# EtherWiz_3K4KNic.net
KiCad netlist of a schematic drawn in Altium Designer
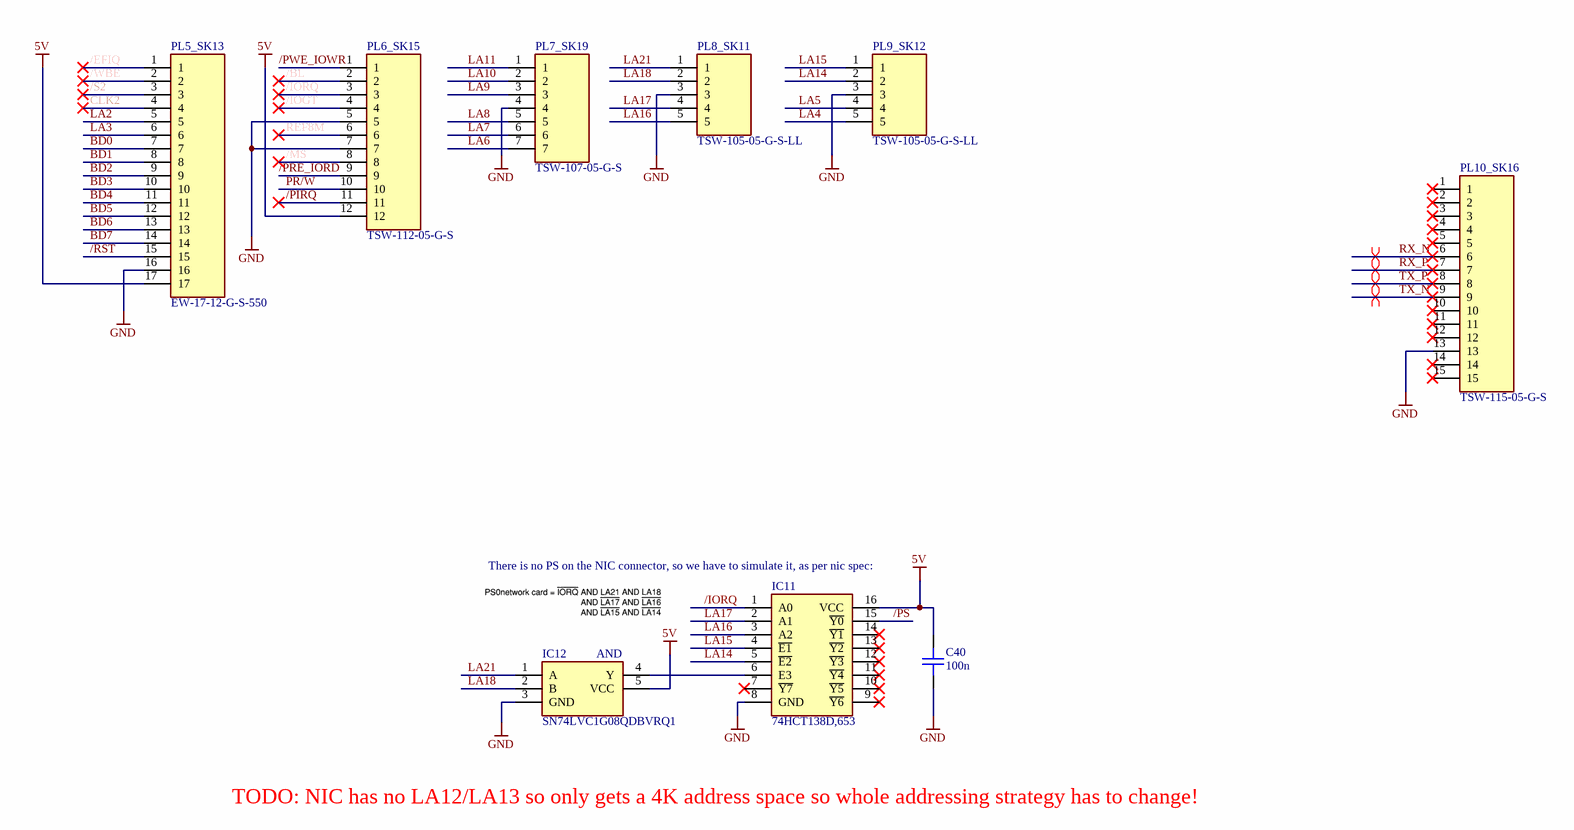
[diagram p0: EtherWiz_3K4KNic.SchDoc]

(export (version "E")
  (design (tool "Eeschema 10.0.6"))
  (components
    (comp (ref "C40")
      (value "100n")
      (footprint "CAPC1608L")
      (description "CAP 100nF, 0603, 50V, X7R, 10%")
      (fields
        (field (name "DISTRIBUTOR1 PART NO") "CL10B104KB8NNNC")
        (field (name "DISTRIBUTOR2 PART NO") "311-1344-2-ND")
      )
      (libsource (lib "MCP1002_RevC") (part "CAP_100n_0603_50V_0"))
    )
    (comp (ref "IC11")
      (value "74HCT138D,653")
      (footprint "SamacSys:SOIC127P600X175-16N")
      (description "Integrated Circuit")
      (fields (field (name "MOUSER PART NUMBER") "771-74HCT138D-T"))
      (libsource (lib "*") (part "74HCT138D,653"))
    )
    (comp (ref "IC12")
      (value "SN74LVC1G08QDBVRQ1")
      (footprint "SamacSys:SOT95P280X145-5N")
      (description "Integrated Circuit")
      (fields (field (name "MOUSER PART NUMBER") "595-SN74LVC1G08QDBQ1"))
      (libsource (lib "*") (part "SN74LVC1G08QDBVRQ1"))
    )
    (comp (ref "PL5_SK13")
      (value "EW-17-12-G-S-550")
      (footprint "SamacSys:TSW-117-XX-YY-S")
      (description "Connector")
      (fields (field (name "MANUFACTURER_PART_NUMBER") "TSW-117-05-G-S"))
      (libsource (lib "*") (part "TSW-117-05-G-S"))
    )
    (comp (ref "PL6_SK15")
      (value "TSW-112-05-G-S")
      (footprint "SamacSys:TSW-112-XX-YY-S")
      (description "Connector")
      (libsource (lib "*") (part "TSW-112-05-G-S"))
    )
    (comp (ref "PL7_SK19")
      (value "TSW-107-05-G-S")
      (footprint "SamacSys:TSW-107-XX-YY-S")
      (description "Connector")
      (libsource (lib "*") (part "TSW-107-05-G-S"))
    )
    (comp (ref "PL8_SK11")
      (value "TSW-105-05-G-S-LL")
      (footprint "SamacSys:HDRV5W64P0X254_1X5_1270X254X521P")
      (description "Connector")
      (libsource (lib "*") (part "TSW-105-05-G-S-LL"))
    )
    (comp (ref "PL9_SK12")
      (value "TSW-105-05-G-S-LL")
      (footprint "SamacSys:HDRV5W64P0X254_1X5_1270X254X521P")
      (description "Connector")
      (libsource (lib "*") (part "TSW-105-05-G-S-LL"))
    )
    (comp (ref "PL10_SK16")
      (value "TSW-115-05-G-S")
      (footprint "SamacSys:TSW-115-XX-YY-S")
      (description "Connector")
      (libsource (lib "*") (part "TSW-115-05-G-S"))
    )
  )
  (nets
    (net (code "1") (name "/BD0") (class "Default")
      (node (ref "PL5_SK13") (pin "7") (pinfunction "7_7") (pintype "passive"))
    )
    (net (code "2") (name "/BD1") (class "Default")
      (node (ref "PL5_SK13") (pin "8") (pinfunction "8_8") (pintype "passive"))
    )
    (net (code "3") (name "/BD2") (class "Default")
      (node (ref "PL5_SK13") (pin "9") (pinfunction "9_9") (pintype "passive"))
    )
    (net (code "4") (name "/BD3") (class "Default")
      (node (ref "PL5_SK13") (pin "10") (pinfunction "10_10") (pintype "passive"))
    )
    (net (code "5") (name "/BD4") (class "Default")
      (node (ref "PL5_SK13") (pin "11") (pinfunction "11_11") (pintype "passive"))
    )
    (net (code "6") (name "/BD5") (class "Default")
      (node (ref "PL5_SK13") (pin "12") (pinfunction "12_12") (pintype "passive"))
    )
    (net (code "7") (name "/BD6") (class "Default")
      (node (ref "PL5_SK13") (pin "13") (pinfunction "13_13") (pintype "passive"))
    )
    (net (code "8") (name "/BD7") (class "Default")
      (node (ref "PL5_SK13") (pin "14") (pinfunction "14_14") (pintype "passive"))
    )
    (net (code "9") (name "/CLK2") (class "Default")
      (node (ref "PL5_SK13") (pin "4") (pinfunction "4_4") (pintype "passive+no_connect"))
    )
    (net (code "10") (name "/LA2") (class "Default")
      (node (ref "PL5_SK13") (pin "5") (pinfunction "5_5") (pintype "passive"))
    )
    (net (code "11") (name "/LA3") (class "Default")
      (node (ref "PL5_SK13") (pin "6") (pinfunction "6_6") (pintype "passive"))
    )
    (net (code "12") (name "/LA4") (class "Default")
      (node (ref "PL9_SK12") (pin "5") (pinfunction "5_5") (pintype "passive"))
    )
    (net (code "13") (name "/LA5") (class "Default")
      (node (ref "PL9_SK12") (pin "4") (pinfunction "4_4") (pintype "passive"))
    )
    (net (code "14") (name "/LA6") (class "Default")
      (node (ref "PL7_SK19") (pin "7") (pinfunction "7_7") (pintype "passive"))
    )
    (net (code "15") (name "/LA7") (class "Default")
      (node (ref "PL7_SK19") (pin "6") (pinfunction "6_6") (pintype "passive"))
    )
    (net (code "16") (name "/LA8") (class "Default")
      (node (ref "PL7_SK19") (pin "5") (pinfunction "5_5") (pintype "passive"))
    )
    (net (code "17") (name "/LA9") (class "Default")
      (node (ref "PL7_SK19") (pin "3") (pinfunction "3_3") (pintype "passive"))
    )
    (net (code "18") (name "/LA10") (class "Default")
      (node (ref "PL7_SK19") (pin "2") (pinfunction "2_2") (pintype "passive"))
    )
    (net (code "19") (name "/LA11") (class "Default")
      (node (ref "PL7_SK19") (pin "1") (pinfunction "1_1") (pintype "passive"))
    )
    (net (code "20") (name "/LA14") (class "Default")
      (node (ref "IC11") (pin "5") (pinfunction "~{E2}_5") (pintype "passive"))
      (node (ref "PL9_SK12") (pin "2") (pinfunction "2_2") (pintype "passive"))
    )
    (net (code "21") (name "/LA15") (class "Default")
      (node (ref "IC11") (pin "4") (pinfunction "~{E1}_4") (pintype "passive"))
      (node (ref "PL9_SK12") (pin "1") (pinfunction "1_1") (pintype "passive"))
    )
    (net (code "22") (name "/LA16") (class "Default")
      (node (ref "IC11") (pin "3") (pinfunction "A2_3") (pintype "passive"))
      (node (ref "PL8_SK11") (pin "5") (pinfunction "5_5") (pintype "passive"))
    )
    (net (code "23") (name "/LA17") (class "Default")
      (node (ref "IC11") (pin "2") (pinfunction "A1_2") (pintype "passive"))
      (node (ref "PL8_SK11") (pin "4") (pinfunction "4_4") (pintype "passive"))
    )
    (net (code "24") (name "/LA18") (class "Default")
      (node (ref "IC12") (pin "2") (pinfunction "B_2") (pintype "passive"))
      (node (ref "PL8_SK11") (pin "2") (pinfunction "2_2") (pintype "passive"))
    )
    (net (code "25") (name "/LA21") (class "Default")
      (node (ref "IC12") (pin "1") (pinfunction "A_1") (pintype "passive"))
      (node (ref "PL8_SK11") (pin "1") (pinfunction "1_1") (pintype "passive"))
    )
    (net (code "26") (name "/PR{slash}W") (class "Default")
      (node (ref "PL6_SK15") (pin "10") (pinfunction "10_10") (pintype "passive"))
    )
    (net (code "27") (name "/REF8M") (class "Default")
      (node (ref "PL6_SK15") (pin "6") (pinfunction "6_6") (pintype "passive+no_connect"))
    )
    (net (code "28") (name "/RX_N") (class "Default")
      (node (ref "PL10_SK16") (pin "6") (pinfunction "6_6") (pintype "passive+no_connect"))
    )
    (net (code "29") (name "/RX_P") (class "Default")
      (node (ref "PL10_SK16") (pin "7") (pinfunction "7_7") (pintype "passive+no_connect"))
    )
    (net (code "30") (name "/TX_N") (class "Default")
      (node (ref "PL10_SK16") (pin "9") (pinfunction "9_9") (pintype "passive+no_connect"))
    )
    (net (code "31") (name "/TX_P") (class "Default")
      (node (ref "PL10_SK16") (pin "8") (pinfunction "8_8") (pintype "passive+no_connect"))
    )
    (net (code "32") (name "/{slash}BL") (class "Default")
      (node (ref "PL6_SK15") (pin "2") (pinfunction "2_2") (pintype "passive+no_connect"))
    )
    (net (code "33") (name "/{slash}EFIQ") (class "Default")
      (node (ref "PL5_SK13") (pin "1") (pinfunction "1_1") (pintype "passive+no_connect"))
    )
    (net (code "34") (name "/{slash}IOGT") (class "Default")
      (node (ref "PL6_SK15") (pin "4") (pinfunction "4_4") (pintype "passive+no_connect"))
    )
    (net (code "35") (name "/{slash}IORQ") (class "Default")
      (node (ref "IC11") (pin "1") (pinfunction "A0_1") (pintype "passive"))
      (node (ref "PL6_SK15") (pin "3") (pinfunction "3_3") (pintype "passive"))
    )
    (net (code "36") (name "/{slash}MS") (class "Default")
      (node (ref "PL6_SK15") (pin "8") (pinfunction "8_8") (pintype "passive+no_connect"))
    )
    (net (code "37") (name "/{slash}PIRQ") (class "Default")
      (node (ref "PL6_SK15") (pin "11") (pinfunction "11_11") (pintype "passive+no_connect"))
    )
    (net (code "38") (name "/{slash}PRE_IORD") (class "Default")
      (node (ref "PL6_SK15") (pin "9") (pinfunction "9_9") (pintype "passive"))
    )
    (net (code "39") (name "/{slash}PS") (class "Default")
      (node (ref "IC11") (pin "15") (pinfunction "~{Y0}_15") (pintype "passive"))
    )
    (net (code "40") (name "/{slash}PWE_IOWR") (class "Default")
      (node (ref "PL6_SK15") (pin "1") (pinfunction "1_1") (pintype "passive"))
    )
    (net (code "41") (name "/{slash}RST") (class "Default")
      (node (ref "PL5_SK13") (pin "15") (pinfunction "15_15") (pintype "passive"))
    )
    (net (code "42") (name "/{slash}S2") (class "Default")
      (node (ref "PL5_SK13") (pin "3") (pinfunction "3_3") (pintype "passive+no_connect"))
    )
    (net (code "43") (name "/{slash}WBE") (class "Default")
      (node (ref "PL5_SK13") (pin "2") (pinfunction "2_2") (pintype "passive+no_connect"))
    )
    (net (code "44") (name "5V") (class "Default")
      (node (ref "C40") (pin "2") (pintype "passive"))
      (node (ref "IC11") (pin "16") (pinfunction "VCC_16") (pintype "passive"))
      (node (ref "IC12") (pin "5") (pinfunction "VCC_5") (pintype "power_in"))
      (node (ref "PL5_SK13") (pin "17") (pinfunction "17_17") (pintype "passive"))
      (node (ref "PL6_SK15") (pin "12") (pinfunction "12_12") (pintype "passive"))
    )
    (net (code "45") (name "GND") (class "Default")
      (node (ref "C40") (pin "1") (pintype "passive"))
      (node (ref "IC11") (pin "8") (pinfunction "GND_8") (pintype "passive"))
      (node (ref "IC12") (pin "3") (pinfunction "GND_3") (pintype "power_in"))
      (node (ref "PL10_SK16") (pin "13") (pinfunction "13_13") (pintype "passive"))
      (node (ref "PL5_SK13") (pin "16") (pinfunction "16_16") (pintype "passive"))
      (node (ref "PL6_SK15") (pin "5") (pinfunction "5_5") (pintype "passive"))
      (node (ref "PL6_SK15") (pin "7") (pinfunction "7_7") (pintype "passive"))
      (node (ref "PL7_SK19") (pin "4") (pinfunction "4_4") (pintype "passive"))
      (node (ref "PL8_SK11") (pin "3") (pinfunction "3_3") (pintype "passive"))
      (node (ref "PL9_SK12") (pin "3") (pinfunction "3_3") (pintype "passive"))
    )
    (net (code "46") (name "Net-(IC11-E3)") (class "Default")
      (node (ref "IC11") (pin "6") (pinfunction "E3_6") (pintype "passive"))
      (node (ref "IC12") (pin "4") (pinfunction "Y_4") (pintype "passive"))
    )
    (net (code "47") (name "unconnected-(IC11-~{Y1}-Pad14)") (class "Default")
      (node (ref "IC11") (pin "14") (pinfunction "~{Y1}_14") (pintype "passive+no_connect"))
    )
    (net (code "48") (name "unconnected-(IC11-~{Y2}-Pad13)") (class "Default")
      (node (ref "IC11") (pin "13") (pinfunction "~{Y2}_13") (pintype "passive+no_connect"))
    )
    (net (code "49") (name "unconnected-(IC11-~{Y3}-Pad12)") (class "Default")
      (node (ref "IC11") (pin "12") (pinfunction "~{Y3}_12") (pintype "passive+no_connect"))
    )
    (net (code "50") (name "unconnected-(IC11-~{Y4}-Pad11)") (class "Default")
      (node (ref "IC11") (pin "11") (pinfunction "~{Y4}_11") (pintype "passive+no_connect"))
    )
    (net (code "51") (name "unconnected-(IC11-~{Y5}-Pad10)") (class "Default")
      (node (ref "IC11") (pin "10") (pinfunction "~{Y5}_10") (pintype "passive+no_connect"))
    )
    (net (code "52") (name "unconnected-(IC11-~{Y6}-Pad9)") (class "Default")
      (node (ref "IC11") (pin "9") (pinfunction "~{Y6}_9") (pintype "passive+no_connect"))
    )
    (net (code "53") (name "unconnected-(IC11-~{Y7}-Pad7)") (class "Default")
      (node (ref "IC11") (pin "7") (pinfunction "~{Y7}_7") (pintype "passive+no_connect"))
    )
    (net (code "54") (name "unconnected-(PL10_SK16-Pad1)") (class "Default")
      (node (ref "PL10_SK16") (pin "1") (pinfunction "1_1") (pintype "passive+no_connect"))
    )
    (net (code "55") (name "unconnected-(PL10_SK16-Pad2)") (class "Default")
      (node (ref "PL10_SK16") (pin "2") (pinfunction "2_2") (pintype "passive+no_connect"))
    )
    (net (code "56") (name "unconnected-(PL10_SK16-Pad3)") (class "Default")
      (node (ref "PL10_SK16") (pin "3") (pinfunction "3_3") (pintype "passive+no_connect"))
    )
    (net (code "57") (name "unconnected-(PL10_SK16-Pad4)") (class "Default")
      (node (ref "PL10_SK16") (pin "4") (pinfunction "4_4") (pintype "passive+no_connect"))
    )
    (net (code "58") (name "unconnected-(PL10_SK16-Pad5)") (class "Default")
      (node (ref "PL10_SK16") (pin "5") (pinfunction "5_5") (pintype "passive+no_connect"))
    )
    (net (code "59") (name "unconnected-(PL10_SK16-Pad10)") (class "Default")
      (node (ref "PL10_SK16") (pin "10") (pinfunction "10_10") (pintype "passive+no_connect"))
    )
    (net (code "60") (name "unconnected-(PL10_SK16-Pad11)") (class "Default")
      (node (ref "PL10_SK16") (pin "11") (pinfunction "11_11") (pintype "passive+no_connect"))
    )
    (net (code "61") (name "unconnected-(PL10_SK16-Pad12)") (class "Default")
      (node (ref "PL10_SK16") (pin "12") (pinfunction "12_12") (pintype "passive+no_connect"))
    )
    (net (code "62") (name "unconnected-(PL10_SK16-Pad14)") (class "Default")
      (node (ref "PL10_SK16") (pin "14") (pinfunction "14_14") (pintype "passive+no_connect"))
    )
    (net (code "63") (name "unconnected-(PL10_SK16-Pad15)") (class "Default")
      (node (ref "PL10_SK16") (pin "15") (pinfunction "15_15") (pintype "passive+no_connect"))
    )
  )
)
